# TH_Sensor.net
KiCad netlist of a schematic drawn in EAGLE
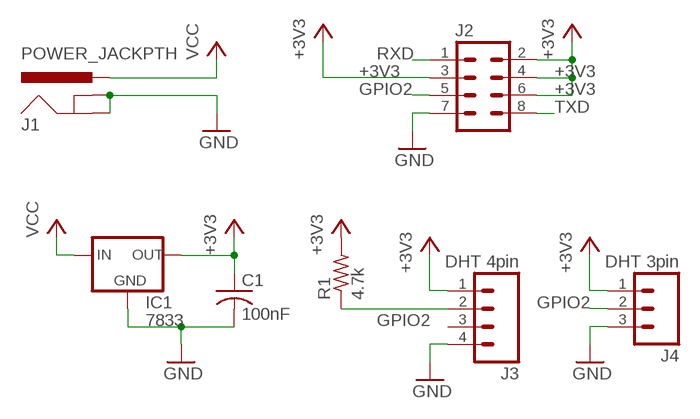
[diagram p0: schematic, sheet 1]

(export (version "E")
  (design (tool "Eeschema 10.0.6"))
  (components
    (comp (ref "C1")
      (value "100nF")
      (footprint "eagle-import:C025-025X050")
      (libsource (lib "eagle-import") (part "C-US025-025X050"))
    )
    (comp (ref "IC1")
      (value "7833")
      (footprint "eagle-import:78XXL")
      (libsource (lib "eagle-import") (part "78XXL"))
    )
    (comp (ref "J1")
      (value "POWER_JACKPTH")
      (footprint "eagle-import:POWER_JACK_PTH")
      (libsource (lib "eagle-import") (part "POWER_JACKPTH"))
    )
    (comp (ref "J2")
      (value "M04X2")
      (footprint "eagle-import:2X4")
      (libsource (lib "eagle-import") (part "M04X2"))
    )
    (comp (ref "J3")
      (value "DHT 4pin")
      (footprint "eagle-import:1X04")
      (libsource (lib "eagle-import") (part "M04PTH"))
    )
    (comp (ref "J4")
      (value "DHT 3pin")
      (footprint "eagle-import:1X03")
      (libsource (lib "eagle-import") (part "M03PTH"))
    )
    (comp (ref "R1")
      (value "4.7k")
      (footprint "eagle-import:0207_10")
      (libsource (lib "eagle-import") (part "R-US_0207/10"))
    )
  )
  (nets
    (net (code "1") (name "+3V3") (class "Default")
      (node (ref "C1") (pin "1") (pinfunction "1_1") (pintype "passive"))
      (node (ref "IC1") (pin "OUT") (pinfunction "OUT_OUT") (pintype "passive"))
      (node (ref "J2") (pin "2") (pinfunction "2_2") (pintype "passive"))
      (node (ref "J2") (pin "3") (pinfunction "3_3") (pintype "passive"))
      (node (ref "J2") (pin "4") (pinfunction "4_4") (pintype "passive"))
      (node (ref "J2") (pin "6") (pinfunction "6_6") (pintype "passive"))
      (node (ref "J3") (pin "1") (pinfunction "1_1") (pintype "passive"))
      (node (ref "J4") (pin "1") (pinfunction "1_1") (pintype "passive"))
      (node (ref "R1") (pin "2") (pinfunction "2_2") (pintype "passive"))
    )
    (net (code "2") (name "/GPIO2") (class "Default")
      (node (ref "J2") (pin "5") (pinfunction "5_5") (pintype "passive"))
      (node (ref "J3") (pin "2") (pinfunction "2_2") (pintype "passive"))
      (node (ref "J4") (pin "2") (pinfunction "2_2") (pintype "passive"))
      (node (ref "R1") (pin "1") (pinfunction "1_1") (pintype "passive"))
    )
    (net (code "3") (name "/RXD") (class "Default")
      (node (ref "J2") (pin "1") (pinfunction "1_1") (pintype "passive"))
    )
    (net (code "4") (name "/TXD") (class "Default")
      (node (ref "J2") (pin "8") (pinfunction "8_8") (pintype "passive"))
    )
    (net (code "5") (name "GND") (class "Default")
      (node (ref "C1") (pin "2") (pinfunction "2_2") (pintype "passive"))
      (node (ref "IC1") (pin "GND") (pinfunction "GND_GND") (pintype "input"))
      (node (ref "J1") (pin "GND") (pinfunction "GND_GND") (pintype "bidirectional"))
      (node (ref "J1") (pin "GNDBREAK") (pinfunction "GNDBREAK_GNDBREAK") (pintype "bidirectional"))
      (node (ref "J2") (pin "7") (pinfunction "7_7") (pintype "passive"))
      (node (ref "J3") (pin "4") (pinfunction "4_4") (pintype "passive"))
      (node (ref "J4") (pin "3") (pinfunction "3_3") (pintype "passive"))
    )
    (net (code "6") (name "VCC") (class "Default")
      (node (ref "IC1") (pin "IN") (pinfunction "IN_IN") (pintype "input"))
      (node (ref "J1") (pin "PWR") (pinfunction "PWR_PWR") (pintype "bidirectional"))
    )
    (net (code "7") (name "unconnected-(J3-Pad3)") (class "Default")
      (node (ref "J3") (pin "3") (pinfunction "3_3") (pintype "passive"))
    )
  )
)
